# 4-POWER.net
KiCad netlist of a schematic drawn in Altium Designer
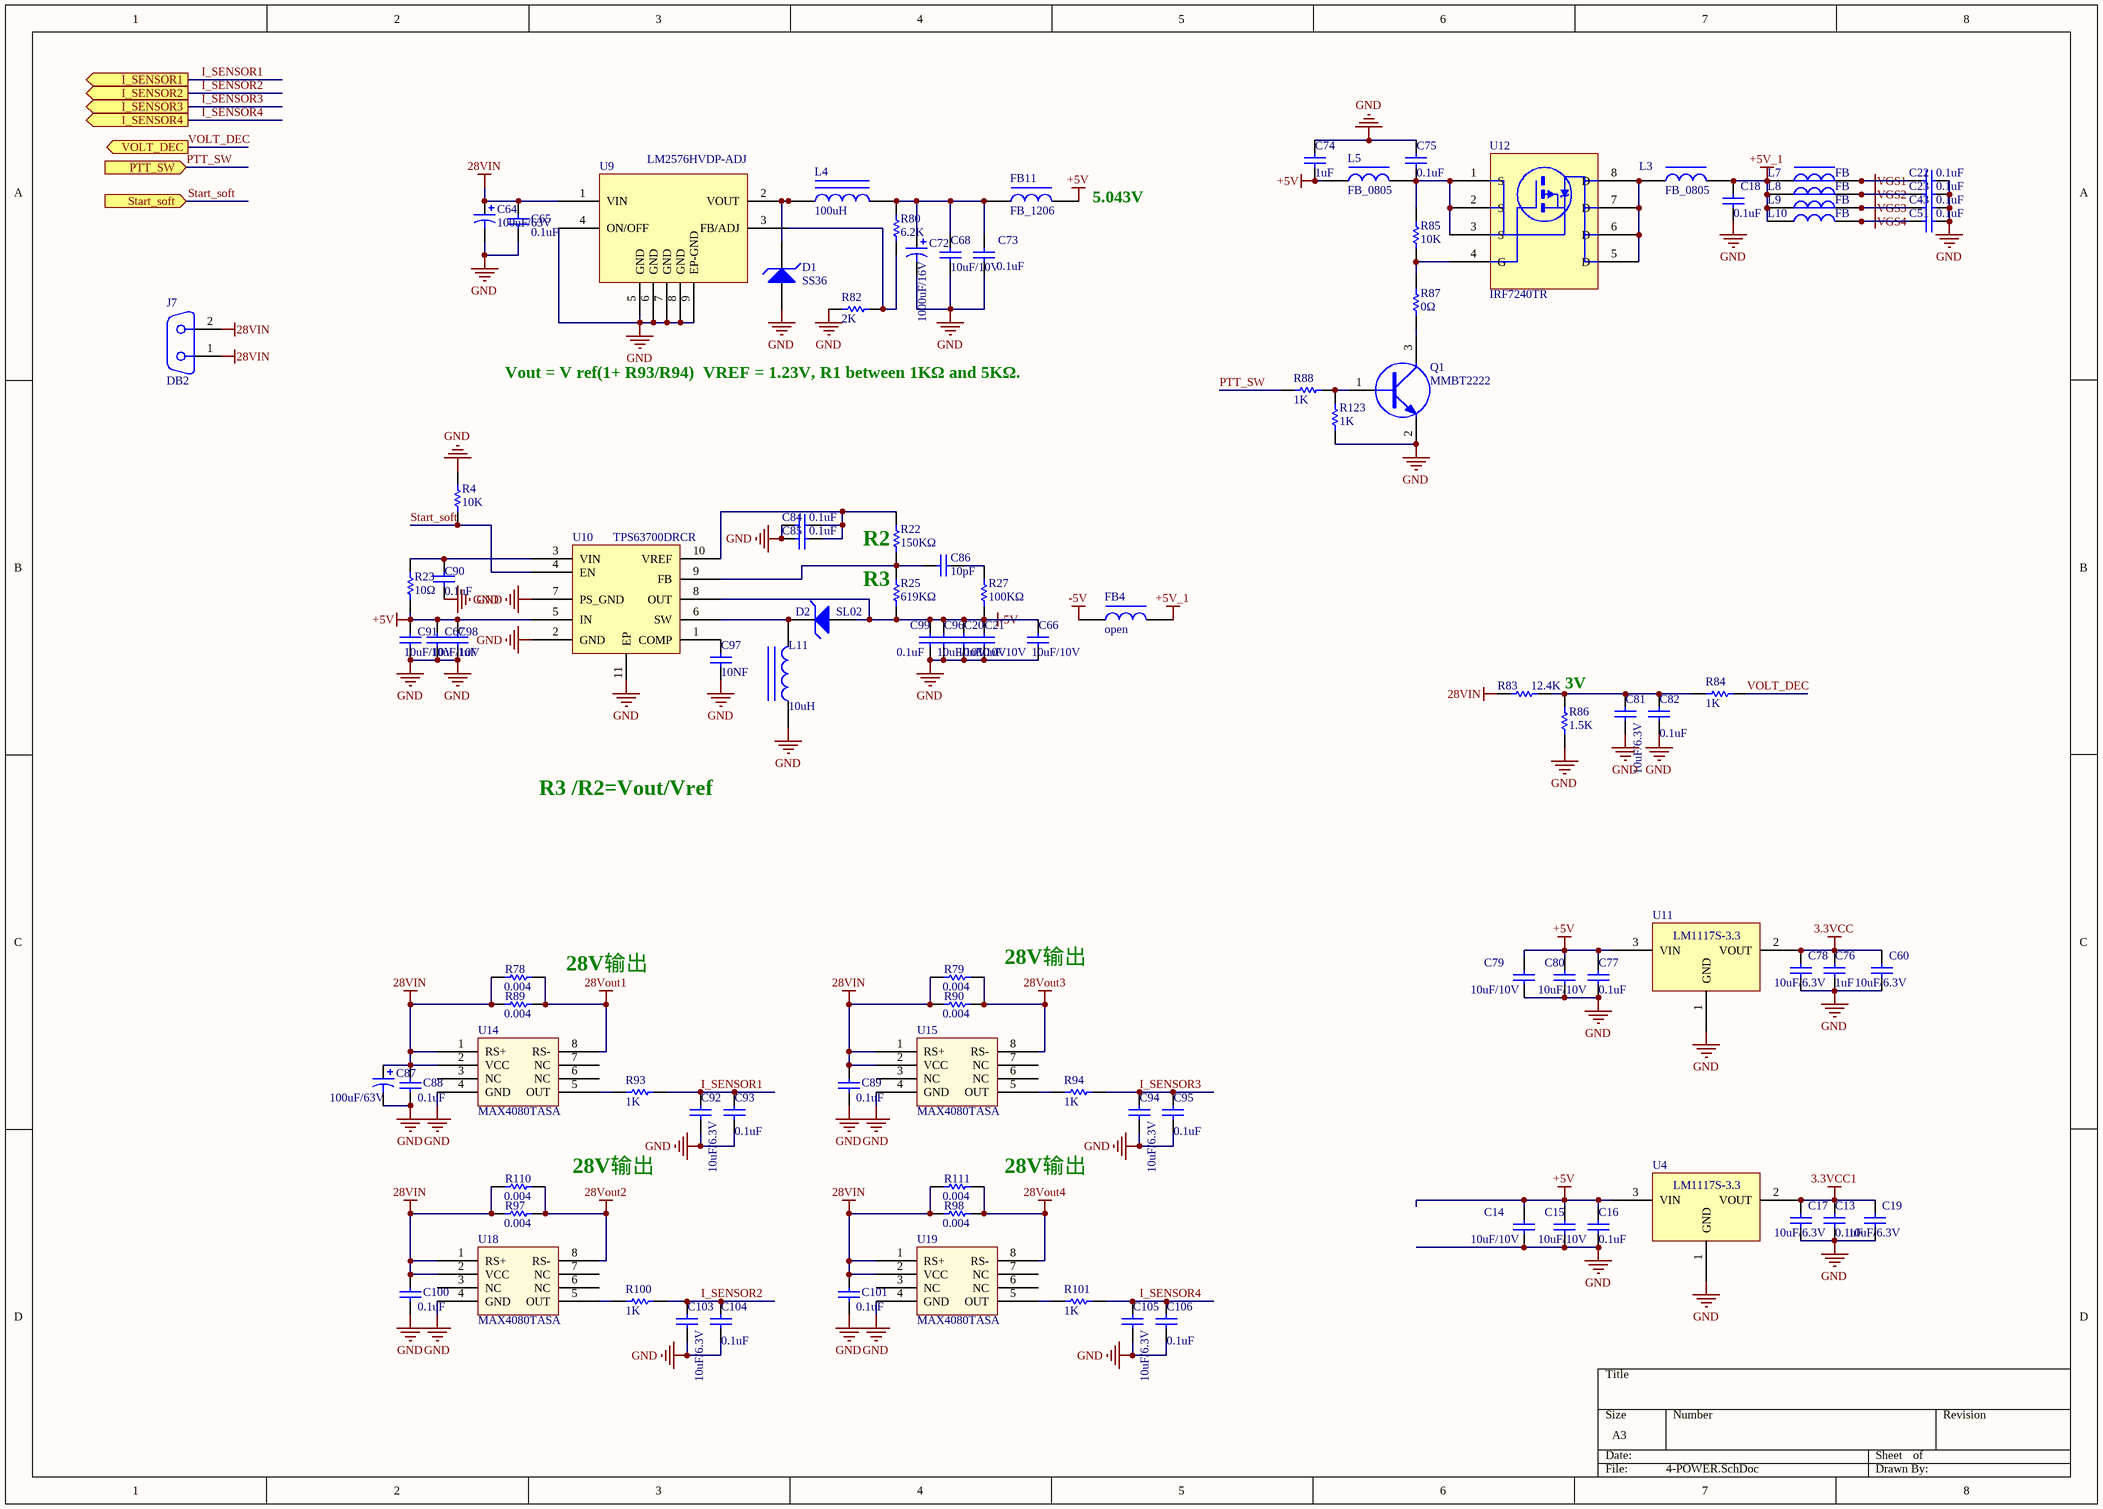
[diagram p0: 4-POWER.SchDoc]

(export (version "E")
  (design (tool "Eeschema 10.0.6"))
  (components
    (comp (ref "C13")
      (value "0.1uF")
      (footprint "C0603")
      (description "贴片电容_GRM188R61A105KA61D_1uF±10%,10V,0603")
      (libsource (lib "20贴片电容0603") (part "1uF贴片电容"))
    )
    (comp (ref "C14")
      (value "10uF/10V")
      (footprint "C0805")
      (description "贴片电容_GRM21BR61A106KE19L_10uF±10%,10V,0805")
      (libsource (lib "21贴片电容0805") (part "10uF贴片电容"))
    )
    (comp (ref "C15")
      (value "10uF/10V")
      (footprint "C0805")
      (description "贴片电容_GRM21BR61A106KE19L_10uF±10%,10V,0805")
      (libsource (lib "21贴片电容0805") (part "10uF贴片电容"))
    )
    (comp (ref "C16")
      (value "0.1uF")
      (footprint "C0603")
      (description "贴片电容_GRM188R71H104KA01D_0.1uF±10%,50V,0603")
      (libsource (lib "20贴片电容0603") (part "0.1uF贴片电容"))
    )
    (comp (ref "C17")
      (value "10uF/6.3V")
      (footprint "C0603")
      (description "贴片电容_GRM188R60J106ME47D_10uF±20%,6.3V,0603")
      (libsource (lib "20贴片电容0603") (part "10uF贴片电容"))
    )
    (comp (ref "C18")
      (value "0.1uF")
      (footprint "C0603")
      (description "GRM188R71H104KA01D")
      (fields (field (name "MPN") "MURATA"))
      (libsource (lib "20贴片电容0603") (part "0.1uF"))
    )
    (comp (ref "C19")
      (value "10uF/6.3V")
      (footprint "C0603")
      (description "贴片电容_GRM188R60J106ME47D_10uF±20%,6.3V,0603")
      (libsource (lib "20贴片电容0603") (part "10uF贴片电容"))
    )
    (comp (ref "C20")
      (value "10uF/10V")
      (footprint "C0805")
      (description "贴片电容_GRM21BR61A106KE19L_10uF±10%,10V,0805")
      (libsource (lib "21贴片电容0805") (part "10uF贴片电容"))
    )
    (comp (ref "C21")
      (value "10uF/10V")
      (footprint "C0805")
      (description "贴片电容_GRM21BR61A106KE19L_10uF±10%,10V,0805")
      (libsource (lib "21贴片电容0805") (part "10uF贴片电容"))
    )
    (comp (ref "C22")
      (value "0.1uF")
      (footprint "C0603")
      (description "GRM188R71H104KA01D")
      (fields (field (name "MPN") "MURATA"))
      (libsource (lib "20贴片电容0603") (part "0.1uF"))
    )
    (comp (ref "C23")
      (value "0.1uF")
      (footprint "C0603")
      (description "GRM188R71H104KA01D")
      (fields (field (name "MPN") "MURATA"))
      (libsource (lib "20贴片电容0603") (part "0.1uF"))
    )
    (comp (ref "C43")
      (value "0.1uF")
      (footprint "C0603")
      (description "GRM188R71H104KA01D")
      (fields (field (name "MPN") "MURATA"))
      (libsource (lib "20贴片电容0603") (part "0.1uF"))
    )
    (comp (ref "C51")
      (value "0.1uF")
      (footprint "C0603")
      (description "GRM188R71H104KA01D")
      (fields (field (name "MPN") "MURATA"))
      (libsource (lib "20贴片电容0603") (part "0.1uF"))
    )
    (comp (ref "C60")
      (value "10uF/6.3V")
      (footprint "C0603")
      (description "贴片电容_GRM188R60J106ME47D_10uF±20%,6.3V,0603")
      (libsource (lib "20贴片电容0603") (part "10uF贴片电容"))
    )
    (comp (ref "C64")
      (value "100uF/63V")
      (footprint "ECAP2SM_10R4x10R4")
      (description "贴片电解电容_VEJ101M1JTR-1010_100uF/63V,±20%,表贴D10*H10")
      (libsource (lib "24电解电容") (part "100uF/63V"))
    )
    (comp (ref "C65")
      (value "0.1uF")
      (footprint "C0603")
      (description "贴片电容_GRM188R71H104KA01D_0.1uF±10%,50V,0603")
      (libsource (lib "20贴片电容0603") (part "0.1uF贴片电容"))
    )
    (comp (ref "C66")
      (value "10uF/10V")
      (footprint "C0805")
      (description "贴片电容_GRM21BR61A106KE19L_10uF±10%,10V,0805")
      (libsource (lib "21贴片电容0805") (part "10uF贴片电容"))
    )
    (comp (ref "C67")
      (value "10uF/10V")
      (footprint "C0805")
      (description "贴片电容_GRM21BR61A106KE19L_10uF±10%,10V,0805")
      (libsource (lib "21贴片电容0805") (part "10uF贴片电容"))
    )
    (comp (ref "C68")
      (value "10uF/10V")
      (footprint "C0805")
      (description "贴片电容_GRM21BR61A106KE19L_10uF±10%,10V,0805")
      (libsource (lib "21贴片电容0805") (part "10uF贴片电容"))
    )
    (comp (ref "C72")
      (value "1000uF/16V")
      (footprint "ECAP2SM_10R4x10R4")
      (description "贴片电解电容_VE102M1CTR-1010_1000uF/16V,±20%,表贴10*10")
      (libsource (lib "24电解电容") (part "1000uF/16V"))
    )
    (comp (ref "C73")
      (value "0.1uF")
      (footprint "C0603")
      (description "贴片电容_GRM188R71H104KA01D_0.1uF±10%,50V,0603")
      (libsource (lib "20贴片电容0603") (part "0.1uF贴片电容"))
    )
    (comp (ref "C74")
      (value "1uF")
      (footprint "C0603")
      (description "贴片电容_GRM188R61A105KA61D_1uF±10%,10V,0603")
      (libsource (lib "20贴片电容0603") (part "1uF贴片电容"))
    )
    (comp (ref "C75")
      (value "0.1uF")
      (footprint "C0603")
      (description "贴片电容_GRM188R71H104KA01D_0.1uF±10%,50V,0603")
      (libsource (lib "20贴片电容0603") (part "0.1uF贴片电容"))
    )
    (comp (ref "C76")
      (value "1uF")
      (footprint "C0603")
      (description "贴片电容_GRM188R61A105KA61D_1uF±10%,10V,0603")
      (libsource (lib "20贴片电容0603") (part "1uF贴片电容"))
    )
    (comp (ref "C77")
      (value "0.1uF")
      (footprint "C0603")
      (description "贴片电容_GRM188R71H104KA01D_0.1uF±10%,50V,0603")
      (libsource (lib "20贴片电容0603") (part "0.1uF贴片电容"))
    )
    (comp (ref "C78")
      (value "10uF/6.3V")
      (footprint "C0603")
      (description "贴片电容_GRM188R60J106ME47D_10uF±20%,6.3V,0603")
      (libsource (lib "20贴片电容0603") (part "10uF贴片电容"))
    )
    (comp (ref "C79")
      (value "10uF/10V")
      (footprint "C0805")
      (description "贴片电容_GRM21BR61A106KE19L_10uF±10%,10V,0805")
      (libsource (lib "21贴片电容0805") (part "10uF贴片电容"))
    )
    (comp (ref "C80")
      (value "10uF/10V")
      (footprint "C0805")
      (description "贴片电容_GRM21BR61A106KE19L_10uF±10%,10V,0805")
      (libsource (lib "21贴片电容0805") (part "10uF贴片电容"))
    )
    (comp (ref "C81")
      (value "10uF/6.3V")
      (footprint "C0603")
      (description "贴片电容_GRM188R60J106ME47D_10uF±20%,6.3V,0603")
      (libsource (lib "20贴片电容0603") (part "10uF贴片电容"))
    )
    (comp (ref "C82")
      (value "0.1uF")
      (footprint "C0603")
      (description "贴片电容_GRM188R71H104KA01D_0.1uF±10%,50V,0603")
      (libsource (lib "20贴片电容0603") (part "0.1uF贴片电容"))
    )
    (comp (ref "C84")
      (value "0.1uF")
      (footprint "C0603")
      (description "GRM188R71H104KA01D")
      (fields (field (name "MPN") "MURATA"))
      (libsource (lib "20贴片电容0603") (part "0.1uF"))
    )
    (comp (ref "C85")
      (value "0.1uF")
      (footprint "C0603")
      (description "GRM188R71H104KA01D")
      (fields (field (name "MPN") "MURATA"))
      (libsource (lib "20贴片电容0603") (part "0.1uF"))
    )
    (comp (ref "C86")
      (value "10pF")
      (footprint "C0603")
      (description "贴片电容_0603CG100J500NT_10pF±5%,50V,0603")
      (libsource (lib "20贴片电容0603") (part "10pF贴片电容"))
    )
    (comp (ref "C87")
      (value "100uF/63V")
      (footprint "ECAP2SM_10R4x10R4")
      (description "贴片电解电容_VEJ101M1JTR-1010_100uF/63V,±20%,表贴D10*H10")
      (libsource (lib "24电解电容") (part "100uF/63V"))
    )
    (comp (ref "C88")
      (value "0.1uF")
      (footprint "C0603")
      (description "贴片电容_GRM188R71H104KA01D_0.1uF±10%,50V,0603")
      (libsource (lib "20贴片电容0603") (part "0.1uF贴片电容"))
    )
    (comp (ref "C89")
      (value "0.1uF")
      (footprint "C0603")
      (description "贴片电容_GRM188R71H104KA01D_0.1uF±10%,50V,0603")
      (libsource (lib "20贴片电容0603") (part "0.1uF贴片电容"))
    )
    (comp (ref "C90")
      (value "0.1uF")
      (footprint "C0603")
      (description "GRM188R71H104KA01D")
      (fields (field (name "MPN") "MURATA"))
      (libsource (lib "20贴片电容0603") (part "0.1uF"))
    )
    (comp (ref "C91")
      (value "10uF/10V")
      (footprint "C0805")
      (description "贴片电容_GRM21BR61A106KE19L_10uF±10%,10V,0805")
      (libsource (lib "21贴片电容0805") (part "10uF贴片电容"))
    )
    (comp (ref "C92")
      (value "10uF/6.3V")
      (footprint "C0603")
      (description "贴片电容_GRM188R60J106ME47D_10uF±20%,6.3V,0603")
      (libsource (lib "20贴片电容0603") (part "10uF贴片电容"))
    )
    (comp (ref "C93")
      (value "0.1uF")
      (footprint "C0603")
      (description "贴片电容_GRM188R71H104KA01D_0.1uF±10%,50V,0603")
      (libsource (lib "20贴片电容0603") (part "0.1uF贴片电容"))
    )
    (comp (ref "C94")
      (value "10uF/6.3V")
      (footprint "C0603")
      (description "贴片电容_GRM188R60J106ME47D_10uF±20%,6.3V,0603")
      (libsource (lib "20贴片电容0603") (part "10uF贴片电容"))
    )
    (comp (ref "C95")
      (value "0.1uF")
      (footprint "C0603")
      (description "贴片电容_GRM188R71H104KA01D_0.1uF±10%,50V,0603")
      (libsource (lib "20贴片电容0603") (part "0.1uF贴片电容"))
    )
    (comp (ref "C96")
      (value "10uF/10V")
      (footprint "C0805")
      (description "贴片电容_GRM21BR61A106KE19L_10uF±10%,10V,0805")
      (libsource (lib "21贴片电容0805") (part "10uF贴片电容"))
    )
    (comp (ref "C97")
      (value "10NF")
      (footprint "C0603")
      (description "0603,10NF,50V,±10％,X7R")
      (libsource (lib "20贴片电容0603") (part "0.1uF"))
    )
    (comp (ref "C98") (value "1uF") (footprint "C0603") (libsource (lib "20贴片电容0603") (part "0.1uF")))
    (comp (ref "C99")
      (value "0.1uF")
      (footprint "C0603")
      (description "GRM188R71H104KA01D")
      (fields (field (name "MPN") "MURATA"))
      (libsource (lib "20贴片电容0603") (part "0.1uF"))
    )
    (comp (ref "C100")
      (value "0.1uF")
      (footprint "C0603")
      (description "贴片电容_GRM188R71H104KA01D_0.1uF±10%,50V,0603")
      (libsource (lib "20贴片电容0603") (part "0.1uF贴片电容"))
    )
    (comp (ref "C101")
      (value "0.1uF")
      (footprint "C0603")
      (description "贴片电容_GRM188R71H104KA01D_0.1uF±10%,50V,0603")
      (libsource (lib "20贴片电容0603") (part "0.1uF贴片电容"))
    )
    (comp (ref "C103")
      (value "10uF/6.3V")
      (footprint "C0603")
      (description "贴片电容_GRM188R60J106ME47D_10uF±20%,6.3V,0603")
      (libsource (lib "20贴片电容0603") (part "10uF贴片电容"))
    )
    (comp (ref "C104")
      (value "0.1uF")
      (footprint "C0603")
      (description "贴片电容_GRM188R71H104KA01D_0.1uF±10%,50V,0603")
      (libsource (lib "20贴片电容0603") (part "0.1uF贴片电容"))
    )
    (comp (ref "C105")
      (value "10uF/6.3V")
      (footprint "C0603")
      (description "贴片电容_GRM188R60J106ME47D_10uF±20%,6.3V,0603")
      (libsource (lib "20贴片电容0603") (part "10uF贴片电容"))
    )
    (comp (ref "C106")
      (value "0.1uF")
      (footprint "C0603")
      (description "贴片电容_GRM188R71H104KA01D_0.1uF±10%,50V,0603")
      (libsource (lib "20贴片电容0603") (part "0.1uF贴片电容"))
    )
    (comp (ref "D1")
      (value "SS36")
      (footprint "DO-214AC")
      (description "肖特基整流二极管_SS36_封装SMA,3A/60V")
      (libsource (lib "40二极管") (part "肖特基整流二极管_SS36"))
    )
    (comp (ref "D2")
      (value "SL02")
      (footprint "SL02")
      (description "肖特基整流二极管_SL02_1.1A/20V")
      (libsource (lib "40二极管") (part "肖特基整流二极管_SS36"))
    )
    (comp (ref "FB4")
      (value "open")
      (footprint "L0805")
      (description "贴片磁珠_600R,0805")
      (libsource (lib "33贴片磁珠0805") (part "0805贴片磁珠"))
    )
    (comp (ref "FB11")
      (value "FB_1206")
      (footprint "L1206")
      (description "贴片磁珠_30R,6A,1206")
      (libsource (lib "34贴片磁珠1206") (part "1206贴片磁珠"))
    )
    (comp (ref "J7")
      (value "DB2")
      (footprint "DB2TM-VM")
      (description "连接器_DB2公头,电源接头")
      (libsource (lib "91连接器") (part "DB2公头座子"))
    )
    (comp (ref "L3")
      (value "FB_0805")
      (footprint "L0805")
      (description "贴片磁珠_600R,0805")
      (libsource (lib "33贴片磁珠0805") (part "0805贴片磁珠"))
    )
    (comp (ref "L4")
      (value "100uH")
      (footprint "PL2SM-12R5x12R5")
      (description "贴片功率电感_SLF12575T-101M1R9-PF_100uH±20%,额定电流1.9A,12.5x12.5")
      (libsource (lib "32贴片功率电感") (part "100uH贴片功率电感"))
    )
    (comp (ref "L5")
      (value "FB_0805")
      (footprint "L0805")
      (description "贴片磁珠_600R,0805")
      (libsource (lib "33贴片磁珠0805") (part "0805贴片磁珠"))
    )
    (comp (ref "L7")
      (value "FB")
      (footprint "L0805")
      (description "贴片磁珠_600R,0805")
      (libsource (lib "33贴片磁珠0805") (part "0805贴片磁珠"))
    )
    (comp (ref "L8")
      (value "FB")
      (footprint "L0805")
      (description "贴片磁珠_600R,0805")
      (libsource (lib "33贴片磁珠0805") (part "0805贴片磁珠"))
    )
    (comp (ref "L9")
      (value "FB")
      (footprint "L0805")
      (description "贴片磁珠_600R,0805")
      (libsource (lib "33贴片磁珠0805") (part "0805贴片磁珠"))
    )
    (comp (ref "L10")
      (value "FB")
      (footprint "L0805")
      (description "贴片磁珠_600R,0805")
      (libsource (lib "33贴片磁珠0805") (part "0805贴片磁珠"))
    )
    (comp (ref "L11")
      (value "10uH")
      (footprint "PL2SM-3R0x3R0")
      (description "SLF6025-10uH")
      (libsource (lib "35贴片功率电感") (part "SLF6025T-100M1R0-PF"))
    )
    (comp (ref "Q1")
      (value "MMBT2222")
      (footprint "SOT23-3")
      (description "NPN三极管_MMBT2222_表贴SOT23")
      (libsource (lib "50三极管") (part "MMBT2222"))
    )
    (comp (ref "R4")
      (value "10K")
      (footprint "R0603")
      (description "贴片电阻_10K±5%,0603")
      (libsource (lib "10贴片电阻0603") (part "10K贴片电阻"))
    )
    (comp (ref "R22") (value "150KΩ") (footprint "R0603") (libsource (lib "10贴片电阻0603") (part "10Ω贴片电阻")))
    (comp (ref "R23")
      (value "10Ω")
      (footprint "R0603")
      (description "贴片电阻_10Ω±5%,0603")
      (libsource (lib "10贴片电阻0603") (part "10Ω贴片电阻"))
    )
    (comp (ref "R25") (value "619KΩ") (footprint "R0603") (libsource (lib "10贴片电阻0603") (part "10Ω贴片电阻")))
    (comp (ref "R27") (value "100KΩ") (footprint "R0603") (libsource (lib "10贴片电阻0603") (part "10Ω贴片电阻")))
    (comp (ref "R78")
      (value "0.004")
      (footprint "R2512")
      (description "贴片电阻_LR12DTDSR004_0.004±5%,2W,2512")
      (libsource (lib "15贴片检流电阻") (part "0.004Ω检流电阻-大封装"))
    )
    (comp (ref "R79")
      (value "0.004")
      (footprint "R2512")
      (description "贴片电阻_LR12DTDSR004_0.004±5%,2W,2512")
      (libsource (lib "15贴片检流电阻") (part "0.004Ω检流电阻-大封装"))
    )
    (comp (ref "R80")
      (value "6.2K")
      (footprint "R0603")
      (description "贴片电阻_6.2K±5%,0603")
      (libsource (lib "10贴片电阻0603") (part "6.2K贴片电阻"))
    )
    (comp (ref "R82")
      (value "2K")
      (footprint "R0603")
      (description "贴片电阻_2K±5%,0603")
      (libsource (lib "10贴片电阻0603") (part "2K贴片电阻"))
    )
    (comp (ref "R83")
      (value "12.4K")
      (footprint "R0603")
      (description "贴片电阻_12.4K±1%,0603")
      (libsource (lib "10贴片电阻0603") (part "12.4K贴片电阻"))
    )
    (comp (ref "R84")
      (value "1K")
      (footprint "C0603")
      (description "贴片电阻_1K±5%,0603")
      (libsource (lib "10贴片电阻0603") (part "1K贴片电阻"))
    )
    (comp (ref "R85")
      (value "10K")
      (footprint "R0603")
      (description "贴片电阻_10K±5%,0603")
      (libsource (lib "10贴片电阻0603") (part "10K贴片电阻"))
    )
    (comp (ref "R86")
      (value "1.5K")
      (footprint "R0603")
      (description "贴片电阻_1.5K±5%,0603")
      (libsource (lib "10贴片电阻0603") (part "1.5K贴片电阻"))
    )
    (comp (ref "R87")
      (value "0Ω")
      (footprint "R0603")
      (description "贴片电阻_0Ω±5%,0603")
      (libsource (lib "10贴片电阻0603") (part "0Ω贴片电阻"))
    )
    (comp (ref "R88")
      (value "1K")
      (footprint "R0603")
      (description "贴片电阻_1K±5%,0603")
      (libsource (lib "10贴片电阻0603") (part "1K贴片电阻"))
    )
    (comp (ref "R89")
      (value "0.004")
      (footprint "R2512")
      (description "贴片电阻_LR12DTDSR004_0.004±5%,2W,2512")
      (libsource (lib "15贴片检流电阻") (part "0.004Ω检流电阻-大封装"))
    )
    (comp (ref "R90")
      (value "0.004")
      (footprint "R2512")
      (description "贴片电阻_LR12DTDSR004_0.004±5%,2W,2512")
      (libsource (lib "15贴片检流电阻") (part "0.004Ω检流电阻-大封装"))
    )
    (comp (ref "R93")
      (value "1K")
      (footprint "R0603")
      (description "贴片电阻_1K±5%,0603")
      (libsource (lib "10贴片电阻0603") (part "1K贴片电阻"))
    )
    (comp (ref "R94")
      (value "1K")
      (footprint "R0603")
      (description "贴片电阻_1K±5%,0603")
      (libsource (lib "10贴片电阻0603") (part "1K贴片电阻"))
    )
    (comp (ref "R97")
      (value "0.004")
      (footprint "R2512")
      (description "贴片电阻_LR12DTDSR004_0.004±5%,2W,2512")
      (libsource (lib "15贴片检流电阻") (part "0.004Ω检流电阻-大封装"))
    )
    (comp (ref "R98")
      (value "0.004")
      (footprint "R2512")
      (description "贴片电阻_LR12DTDSR004_0.004±5%,2W,2512")
      (libsource (lib "15贴片检流电阻") (part "0.004Ω检流电阻-大封装"))
    )
    (comp (ref "R100")
      (value "1K")
      (footprint "R0603")
      (description "贴片电阻_1K±5%,0603")
      (libsource (lib "10贴片电阻0603") (part "1K贴片电阻"))
    )
    (comp (ref "R101")
      (value "1K")
      (footprint "R0603")
      (description "贴片电阻_1K±5%,0603")
      (libsource (lib "10贴片电阻0603") (part "1K贴片电阻"))
    )
    (comp (ref "R110")
      (value "0.004")
      (footprint "R2512")
      (description "贴片电阻_LR12DTDSR004_0.004±5%,2W,2512")
      (libsource (lib "15贴片检流电阻") (part "0.004Ω检流电阻-大封装"))
    )
    (comp (ref "R111")
      (value "0.004")
      (footprint "R2512")
      (description "贴片电阻_LR12DTDSR004_0.004±5%,2W,2512")
      (libsource (lib "15贴片检流电阻") (part "0.004Ω检流电阻-大封装"))
    )
    (comp (ref "R123")
      (value "1K")
      (footprint "R0603")
      (description "贴片电阻_1K±5%,0603")
      (libsource (lib "10贴片电阻0603") (part "1K贴片电阻"))
    )
    (comp (ref "U4")
      (value "LM1117S-3.3")
      (footprint "SOT-223")
      (description "LDO_LM1117S-3.3_1A输出,SOT223")
      (libsource (lib "78电源芯片") (part "LM1117S-3.3"))
    )
    (comp (ref "U9")
      (value "LM2576HVDP-ADJ")
      (footprint "SOIC8_1R27_3R9x4R9-1")
      (description "稳压集成电路_LM2576HVDP-ADJ_3A输出,SOIC8")
      (libsource (lib "78电源芯片") (part "LM2576HVDP-ADJ"))
    )
    (comp (ref "U10")
      (value "TPS63700DRCR")
      (footprint "VSON10-0R5-3x3")
      (description "负压转换器_TPS63700DRCR_360mA输出,VSON-10")
      (libsource (lib "78电源芯片") (part "TPS63700DRCR"))
    )
    (comp (ref "U11")
      (value "LM1117S-3.3")
      (footprint "SOT-223")
      (description "LDO_LM1117S-3.3_1A输出,SOT223")
      (libsource (lib "78电源芯片") (part "LM1117S-3.3"))
    )
    (comp (ref "U12")
      (value "IRF7240TR")
      (footprint "SOIC8_1R27_3R9x4R9")
      (description "P-MOSFET_IRF7240TR_SOIC8")
      (libsource (lib "51场效应管") (part "IRF7240TR"))
    )
    (comp (ref "U14")
      (value "MAX4080TASA")
      (footprint "SOIC8_1R27_3R9x4R9")
      (description "电流检测放大器_MAX4080TASA_SOIC8")
      (libsource (lib "79电流检测芯片") (part "MAX4080TASA"))
    )
    (comp (ref "U15")
      (value "MAX4080TASA")
      (footprint "SOIC8_1R27_3R9x4R9")
      (description "电流检测放大器_MAX4080TASA_SOIC8")
      (libsource (lib "79电流检测芯片") (part "MAX4080TASA"))
    )
    (comp (ref "U18")
      (value "MAX4080TASA")
      (footprint "SOIC8_1R27_3R9x4R9")
      (description "电流检测放大器_MAX4080TASA_SOIC8")
      (libsource (lib "79电流检测芯片") (part "MAX4080TASA"))
    )
    (comp (ref "U19")
      (value "MAX4080TASA")
      (footprint "SOIC8_1R27_3R9x4R9")
      (description "电流检测放大器_MAX4080TASA_SOIC8")
      (libsource (lib "79电流检测芯片") (part "MAX4080TASA"))
    )
  )
  (nets
    (net (code "1") (name "+5V") (class "Default")
      (node (ref "C14") (pin "2") (pinfunction "2_2") (pintype "passive"))
      (node (ref "C15") (pin "2") (pinfunction "2_2") (pintype "passive"))
      (node (ref "C16") (pin "2") (pinfunction "2_2") (pintype "passive"))
      (node (ref "C67") (pin "2") (pinfunction "2_2") (pintype "passive"))
      (node (ref "C74") (pin "1") (pinfunction "1_1") (pintype "passive"))
      (node (ref "C77") (pin "2") (pinfunction "2_2") (pintype "passive"))
      (node (ref "C79") (pin "2") (pinfunction "2_2") (pintype "passive"))
      (node (ref "C80") (pin "2") (pinfunction "2_2") (pintype "passive"))
      (node (ref "C91") (pin "2") (pinfunction "2_2") (pintype "passive"))
      (node (ref "C98") (pin "2") (pinfunction "2_2") (pintype "passive"))
      (node (ref "FB11") (pin "2") (pinfunction "2_2") (pintype "passive"))
      (node (ref "L5") (pin "1") (pinfunction "1_1") (pintype "passive"))
      (node (ref "R23") (pin "1") (pinfunction "1_1") (pintype "passive"))
      (node (ref "U10") (pin "5") (pinfunction "IN_5") (pintype "passive"))
      (node (ref "U11") (pin "3") (pinfunction "VIN_3") (pintype "passive"))
      (node (ref "U4") (pin "3") (pinfunction "VIN_3") (pintype "passive"))
    )
    (net (code "2") (name "+5V_1") (class "Default")
      (node (ref "C18") (pin "2") (pinfunction "2_2") (pintype "passive"))
      (node (ref "FB4") (pin "2") (pinfunction "2_2") (pintype "passive"))
      (node (ref "L10") (pin "1") (pinfunction "1_1") (pintype "passive"))
      (node (ref "L3") (pin "2") (pinfunction "2_2") (pintype "passive"))
      (node (ref "L7") (pin "1") (pinfunction "1_1") (pintype "passive"))
      (node (ref "L8") (pin "1") (pinfunction "1_1") (pintype "passive"))
      (node (ref "L9") (pin "1") (pinfunction "1_1") (pintype "passive"))
    )
    (net (code "3") (name "-5V") (class "Default")
      (node (ref "C20") (pin "2") (pinfunction "2_2") (pintype "passive"))
      (node (ref "C21") (pin "2") (pinfunction "2_2") (pintype "passive"))
      (node (ref "C66") (pin "2") (pinfunction "2_2") (pintype "passive"))
      (node (ref "C96") (pin "2") (pinfunction "2_2") (pintype "passive"))
      (node (ref "C99") (pin "2") (pinfunction "2_2") (pintype "passive"))
      (node (ref "D2") (pin "1") (pinfunction "A_1") (pintype "passive"))
      (node (ref "FB4") (pin "1") (pinfunction "1_1") (pintype "passive"))
      (node (ref "R25") (pin "1") (pinfunction "1_1") (pintype "passive"))
      (node (ref "R27") (pin "1") (pinfunction "1_1") (pintype "passive"))
      (node (ref "U10") (pin "8") (pinfunction "OUT_8") (pintype "passive"))
    )
    (net (code "4") (name "/I_SENSOR1") (class "Default")
      (node (ref "C92") (pin "2") (pinfunction "2_2") (pintype "passive"))
      (node (ref "C93") (pin "2") (pinfunction "2_2") (pintype "passive"))
      (node (ref "R93") (pin "2") (pinfunction "2_2") (pintype "passive"))
    )
    (net (code "5") (name "/I_SENSOR2") (class "Default")
      (node (ref "C103") (pin "2") (pinfunction "2_2") (pintype "passive"))
      (node (ref "C104") (pin "2") (pinfunction "2_2") (pintype "passive"))
      (node (ref "R100") (pin "2") (pinfunction "2_2") (pintype "passive"))
    )
    (net (code "6") (name "/I_SENSOR3") (class "Default")
      (node (ref "C94") (pin "2") (pinfunction "2_2") (pintype "passive"))
      (node (ref "C95") (pin "2") (pinfunction "2_2") (pintype "passive"))
      (node (ref "R94") (pin "2") (pinfunction "2_2") (pintype "passive"))
    )
    (net (code "7") (name "/I_SENSOR4") (class "Default")
      (node (ref "C105") (pin "2") (pinfunction "2_2") (pintype "passive"))
      (node (ref "C106") (pin "2") (pinfunction "2_2") (pintype "passive"))
      (node (ref "R101") (pin "2") (pinfunction "2_2") (pintype "passive"))
    )
    (net (code "8") (name "/PTT_SW") (class "Default")
      (node (ref "R88") (pin "1") (pinfunction "1_1") (pintype "passive"))
    )
    (net (code "9") (name "/Start_soft") (class "Default")
      (node (ref "R4") (pin "1") (pinfunction "1_1") (pintype "passive"))
      (node (ref "U10") (pin "4") (pinfunction "EN_4") (pintype "passive"))
    )
    (net (code "10") (name "/VOLT_DEC") (class "Default")
      (node (ref "R84") (pin "1") (pinfunction "1_1") (pintype "passive"))
    )
    (net (code "11") (name "3.3VCC") (class "Default")
      (node (ref "C60") (pin "2") (pinfunction "2_2") (pintype "passive"))
      (node (ref "C76") (pin "2") (pinfunction "2_2") (pintype "passive"))
      (node (ref "C78") (pin "2") (pinfunction "2_2") (pintype "passive"))
      (node (ref "U11") (pin "2") (pinfunction "VOUT_2") (pintype "passive"))
    )
    (net (code "12") (name "3.3VCC1") (class "Default")
      (node (ref "C13") (pin "2") (pinfunction "2_2") (pintype "passive"))
      (node (ref "C17") (pin "2") (pinfunction "2_2") (pintype "passive"))
      (node (ref "C19") (pin "2") (pinfunction "2_2") (pintype "passive"))
      (node (ref "U4") (pin "2") (pinfunction "VOUT_2") (pintype "passive"))
    )
    (net (code "13") (name "28VIN") (class "Default")
      (node (ref "C100") (pin "2") (pinfunction "2_2") (pintype "passive"))
      (node (ref "C101") (pin "2") (pinfunction "2_2") (pintype "passive"))
      (node (ref "C64") (pin "1") (pinfunction "1_1") (pintype "passive"))
      (node (ref "C65") (pin "2") (pinfunction "2_2") (pintype "passive"))
      (node (ref "C87") (pin "1") (pinfunction "1_1") (pintype "passive"))
      (node (ref "C88") (pin "2") (pinfunction "2_2") (pintype "passive"))
      (node (ref "C89") (pin "2") (pinfunction "2_2") (pintype "passive"))
      (node (ref "J7") (pin "1") (pinfunction "1_1") (pintype "passive"))
      (node (ref "J7") (pin "2") (pinfunction "2_2") (pintype "passive"))
      (node (ref "R110") (pin "1") (pinfunction "1_1") (pintype "passive"))
      (node (ref "R111") (pin "1") (pinfunction "1_1") (pintype "passive"))
      (node (ref "R78") (pin "1") (pinfunction "1_1") (pintype "passive"))
      (node (ref "R79") (pin "1") (pinfunction "1_1") (pintype "passive"))
      (node (ref "R83") (pin "1") (pinfunction "1_1") (pintype "passive"))
      (node (ref "R89") (pin "1") (pinfunction "1_1") (pintype "passive"))
      (node (ref "R90") (pin "1") (pinfunction "1_1") (pintype "passive"))
      (node (ref "R97") (pin "1") (pinfunction "1_1") (pintype "passive"))
      (node (ref "R98") (pin "1") (pinfunction "1_1") (pintype "passive"))
      (node (ref "U14") (pin "1") (pinfunction "RS+_1") (pintype "passive"))
      (node (ref "U14") (pin "2") (pinfunction "VCC_2") (pintype "passive"))
      (node (ref "U15") (pin "1") (pinfunction "RS+_1") (pintype "passive"))
      (node (ref "U15") (pin "2") (pinfunction "VCC_2") (pintype "passive"))
      (node (ref "U18") (pin "1") (pinfunction "RS+_1") (pintype "passive"))
      (node (ref "U18") (pin "2") (pinfunction "VCC_2") (pintype "passive"))
      (node (ref "U19") (pin "1") (pinfunction "RS+_1") (pintype "passive"))
      (node (ref "U19") (pin "2") (pinfunction "VCC_2") (pintype "passive"))
      (node (ref "U9") (pin "1") (pinfunction "VIN_1") (pintype "passive"))
    )
    (net (code "14") (name "28Vout1") (class "Default")
      (node (ref "R78") (pin "2") (pinfunction "2_2") (pintype "passive"))
      (node (ref "R89") (pin "2") (pinfunction "2_2") (pintype "passive"))
      (node (ref "U14") (pin "8") (pinfunction "RS-_8") (pintype "passive"))
    )
    (net (code "15") (name "28Vout2") (class "Default")
      (node (ref "R110") (pin "2") (pinfunction "2_2") (pintype "passive"))
      (node (ref "R97") (pin "2") (pinfunction "2_2") (pintype "passive"))
      (node (ref "U18") (pin "8") (pinfunction "RS-_8") (pintype "passive"))
    )
    (net (code "16") (name "28Vout3") (class "Default")
      (node (ref "R79") (pin "2") (pinfunction "2_2") (pintype "passive"))
      (node (ref "R90") (pin "2") (pinfunction "2_2") (pintype "passive"))
      (node (ref "U15") (pin "8") (pinfunction "RS-_8") (pintype "passive"))
    )
    (net (code "17") (name "28Vout4") (class "Default")
      (node (ref "R111") (pin "2") (pinfunction "2_2") (pintype "passive"))
      (node (ref "R98") (pin "2") (pinfunction "2_2") (pintype "passive"))
      (node (ref "U19") (pin "8") (pinfunction "RS-_8") (pintype "passive"))
    )
    (net (code "18") (name "GND") (class "Default")
      (node (ref "C100") (pin "1") (pinfunction "1_1") (pintype "passive"))
      (node (ref "C101") (pin "1") (pinfunction "1_1") (pintype "passive"))
      (node (ref "C103") (pin "1") (pinfunction "1_1") (pintype "passive"))
      (node (ref "C104") (pin "1") (pinfunction "1_1") (pintype "passive"))
      (node (ref "C105") (pin "1") (pinfunction "1_1") (pintype "passive"))
      (node (ref "C106") (pin "1") (pinfunction "1_1") (pintype "passive"))
      (node (ref "C13") (pin "1") (pinfunction "1_1") (pintype "passive"))
      (node (ref "C14") (pin "1") (pinfunction "1_1") (pintype "passive"))
      (node (ref "C15") (pin "1") (pinfunction "1_1") (pintype "passive"))
      (node (ref "C16") (pin "1") (pinfunction "1_1") (pintype "passive"))
      (node (ref "C17") (pin "1") (pinfunction "1_1") (pintype "passive"))
      (node (ref "C18") (pin "1") (pinfunction "1_1") (pintype "passive"))
      (node (ref "C19") (pin "1") (pinfunction "1_1") (pintype "passive"))
      (node (ref "C20") (pin "1") (pinfunction "1_1") (pintype "passive"))
      (node (ref "C21") (pin "1") (pinfunction "1_1") (pintype "passive"))
      (node (ref "C22") (pin "2") (pinfunction "2_2") (pintype "passive"))
      (node (ref "C23") (pin "2") (pinfunction "2_2") (pintype "passive"))
      (node (ref "C43") (pin "2") (pinfunction "2_2") (pintype "passive"))
      (node (ref "C51") (pin "2") (pinfunction "2_2") (pintype "passive"))
      (node (ref "C60") (pin "1") (pinfunction "1_1") (pintype "passive"))
      (node (ref "C64") (pin "2") (pinfunction "2_2") (pintype "passive"))
      (node (ref "C65") (pin "1") (pinfunction "1_1") (pintype "passive"))
      (node (ref "C66") (pin "1") (pinfunction "1_1") (pintype "passive"))
      (node (ref "C67") (pin "1") (pinfunction "1_1") (pintype "passive"))
      (node (ref "C68") (pin "1") (pinfunction "1_1") (pintype "passive"))
      (node (ref "C72") (pin "2") (pinfunction "2_2") (pintype "passive"))
      (node (ref "C73") (pin "1") (pinfunction "1_1") (pintype "passive"))
      (node (ref "C74") (pin "2") (pinfunction "2_2") (pintype "passive"))
      (node (ref "C75") (pin "2") (pinfunction "2_2") (pintype "passive"))
      (node (ref "C76") (pin "1") (pinfunction "1_1") (pintype "passive"))
      (node (ref "C77") (pin "1") (pinfunction "1_1") (pintype "passive"))
      (node (ref "C78") (pin "1") (pinfunction "1_1") (pintype "passive"))
      (node (ref "C79") (pin "1") (pinfunction "1_1") (pintype "passive"))
      (node (ref "C80") (pin "1") (pinfunction "1_1") (pintype "passive"))
      (node (ref "C81") (pin "1") (pinfunction "1_1") (pintype "passive"))
      (node (ref "C82") (pin "1") (pinfunction "1_1") (pintype "passive"))
      (node (ref "C84") (pin "2") (pinfunction "2_2") (pintype "passive"))
      (node (ref "C85") (pin "2") (pinfunction "2_2") (pintype "passive"))
      (node (ref "C87") (pin "2") (pinfunction "2_2") (pintype "passive"))
      (node (ref "C88") (pin "1") (pinfunction "1_1") (pintype "passive"))
      (node (ref "C89") (pin "1") (pinfunction "1_1") (pintype "passive"))
      (node (ref "C90") (pin "1") (pinfunction "1_1") (pintype "passive"))
      (node (ref "C91") (pin "1") (pinfunction "1_1") (pintype "passive"))
      (node (ref "C92") (pin "1") (pinfunction "1_1") (pintype "passive"))
      (node (ref "C93") (pin "1") (pinfunction "1_1") (pintype "passive"))
      (node (ref "C94") (pin "1") (pinfunction "1_1") (pintype "passive"))
      (node (ref "C95") (pin "1") (pinfunction "1_1") (pintype "passive"))
      (node (ref "C96") (pin "1") (pinfunction "1_1") (pintype "passive"))
      (node (ref "C97") (pin "1") (pinfunction "1_1") (pintype "passive"))
      (node (ref "C98") (pin "1") (pinfunction "1_1") (pintype "passive"))
      (node (ref "C99") (pin "1") (pinfunction "1_1") (pintype "passive"))
      (node (ref "D1") (pin "1") (pinfunction "A_1") (pintype "passive"))
      (node (ref "L11") (pin "1") (pinfunction "1_1") (pintype "passive"))
      (node (ref "Q1") (pin "2") (pinfunction "E_2") (pintype "passive"))
      (node (ref "R123") (pin "1") (pinfunction "1_1") (pintype "passive"))
      (node (ref "R4") (pin "2") (pinfunction "2_2") (pintype "passive"))
      (node (ref "R82") (pin "2") (pinfunction "2_2") (pintype "passive"))
      (node (ref "R86") (pin "1") (pinfunction "1_1") (pintype "passive"))
      (node (ref "U10") (pin "11") (pinfunction "EP_11") (pintype "passive"))
      (node (ref "U10") (pin "2") (pinfunction "GND_2") (pintype "passive"))
      (node (ref "U10") (pin "7") (pinfunction "PS_GND_7") (pintype "passive"))
      (node (ref "U11") (pin "1") (pinfunction "GND_1") (pintype "passive"))
      (node (ref "U14") (pin "4") (pinfunction "GND_4") (pintype "passive"))
      (node (ref "U15") (pin "4") (pinfunction "GND_4") (pintype "passive"))
      (node (ref "U18") (pin "4") (pinfunction "GND_4") (pintype "passive"))
      (node (ref "U19") (pin "4") (pinfunction "GND_4") (pintype "passive"))
      (node (ref "U4") (pin "1") (pinfunction "GND_1") (pintype "passive"))
      (node (ref "U9") (pin "4") (pinfunction "ON/OFF_4") (pintype "passive"))
      (node (ref "U9") (pin "5") (pinfunction "GND_5") (pintype "passive"))
      (node (ref "U9") (pin "6") (pinfunction "GND_6") (pintype "passive"))
      (node (ref "U9") (pin "7") (pinfunction "GND_7") (pintype "passive"))
      (node (ref "U9") (pin "8") (pinfunction "GND_8") (pintype "passive"))
      (node (ref "U9") (pin "9") (pinfunction "EP-GND_9") (pintype "passive"))
    )
    (net (code "19") (name "Net-(C68-Pad2)") (class "Default")
      (node (ref "C68") (pin "2") (pinfunction "2_2") (pintype "passive"))
      (node (ref "C72") (pin "1") (pinfunction "1_1") (pintype "passive"))
      (node (ref "C73") (pin "2") (pinfunction "2_2") (pintype "passive"))
      (node (ref "FB11") (pin "1") (pinfunction "1_1") (pintype "passive"))
      (node (ref "L4") (pin "2") (pinfunction "2_2") (pintype "passive"))
      (node (ref "R80") (pin "2") (pinfunction "2_2") (pintype "passive"))
    )
    (net (code "20") (name "Net-(C75-Pad1)") (class "Default")
      (node (ref "C75") (pin "1") (pinfunction "1_1") (pintype "passive"))
      (node (ref "L5") (pin "2") (pinfunction "2_2") (pintype "passive"))
      (node (ref "R85") (pin "2") (pinfunction "2_2") (pintype "passive"))
      (node (ref "U12") (pin "1") (pinfunction "S_1") (pintype "passive"))
      (node (ref "U12") (pin "2") (pinfunction "S_2") (pintype "passive"))
      (node (ref "U12") (pin "3") (pinfunction "S_3") (pintype "passive"))
    )
    (net (code "21") (name "Net-(C81-Pad2)") (class "Default")
      (node (ref "C81") (pin "2") (pinfunction "2_2") (pintype "passive"))
      (node (ref "C82") (pin "2") (pinfunction "2_2") (pintype "passive"))
      (node (ref "R83") (pin "2") (pinfunction "2_2") (pintype "passive"))
      (node (ref "R84") (pin "2") (pinfunction "2_2") (pintype "passive"))
      (node (ref "R86") (pin "2") (pinfunction "2_2") (pintype "passive"))
    )
    (net (code "22") (name "Net-(C86-Pad2)") (class "Default")
      (node (ref "C86") (pin "2") (pinfunction "2_2") (pintype "passive"))
      (node (ref "R27") (pin "2") (pinfunction "2_2") (pintype "passive"))
    )
    (net (code "23") (name "Net-(D1-K)") (class "Default")
      (node (ref "D1") (pin "2") (pinfunction "K_2") (pintype "passive"))
      (node (ref "L4") (pin "1") (pinfunction "1_1") (pintype "passive"))
      (node (ref "U9") (pin "2") (pinfunction "VOUT_2") (pintype "passive"))
    )
    (net (code "24") (name "Net-(D2-K)") (class "Default")
      (node (ref "D2") (pin "2") (pinfunction "K_2") (pintype "passive"))
      (node (ref "L11") (pin "2") (pinfunction "2_2") (pintype "passive"))
      (node (ref "U10") (pin "6") (pinfunction "SW_6") (pintype "passive"))
    )
    (net (code "25") (name "Net-(L3-Pad1)") (class "Default")
      (node (ref "L3") (pin "1") (pinfunction "1_1") (pintype "passive"))
      (node (ref "U12") (pin "5") (pinfunction "D_5") (pintype "passive"))
      (node (ref "U12") (pin "6") (pinfunction "D_6") (pintype "passive"))
      (node (ref "U12") (pin "7") (pinfunction "D_7") (pintype "passive"))
      (node (ref "U12") (pin "8") (pinfunction "D_8") (pintype "passive"))
    )
    (net (code "26") (name "Net-(Q1-B)") (class "Default")
      (node (ref "Q1") (pin "1") (pinfunction "B_1") (pintype "passive"))
      (node (ref "R123") (pin "2") (pinfunction "2_2") (pintype "passive"))
      (node (ref "R88") (pin "2") (pinfunction "2_2") (pintype "passive"))
    )
    (net (code "27") (name "Net-(Q1-C)") (class "Default")
      (node (ref "Q1") (pin "3") (pinfunction "C_3") (pintype "passive"))
      (node (ref "R87") (pin "1") (pinfunction "1_1") (pintype "passive"))
    )
    (net (code "28") (name "Net-(U9-FB{slash}ADJ)") (class "Default")
      (node (ref "R80") (pin "1") (pinfunction "1_1") (pintype "passive"))
      (node (ref "R82") (pin "1") (pinfunction "1_1") (pintype "passive"))
      (node (ref "U9") (pin "3") (pinfunction "FB/ADJ_3") (pintype "passive"))
    )
    (net (code "29") (name "Net-(U10-COMP)") (class "Default")
      (node (ref "C97") (pin "2") (pinfunction "2_2") (pintype "passive"))
      (node (ref "U10") (pin "1") (pinfunction "COMP_1") (pintype "passive"))
    )
    (net (code "30") (name "Net-(U10-FB)") (class "Default")
      (node (ref "C86") (pin "1") (pinfunction "1_1") (pintype "passive"))
      (node (ref "R22") (pin "1") (pinfunction "1_1") (pintype "passive"))
      (node (ref "R25") (pin "2") (pinfunction "2_2") (pintype "passive"))
      (node (ref "U10") (pin "9") (pinfunction "FB_9") (pintype "passive"))
    )
    (net (code "31") (name "Net-(U10-VIN)") (class "Default")
      (node (ref "C90") (pin "2") (pinfunction "2_2") (pintype "passive"))
      (node (ref "R23") (pin "2") (pinfunction "2_2") (pintype "passive"))
      (node (ref "U10") (pin "3") (pinfunction "VIN_3") (pintype "passive"))
    )
    (net (code "32") (name "Net-(U10-VREF)") (class "Default")
      (node (ref "C84") (pin "1") (pinfunction "1_1") (pintype "passive"))
      (node (ref "C85") (pin "1") (pinfunction "1_1") (pintype "passive"))
      (node (ref "R22") (pin "2") (pinfunction "2_2") (pintype "passive"))
      (node (ref "U10") (pin "10") (pinfunction "VREF_10") (pintype "passive"))
    )
    (net (code "33") (name "Net-(U12-G)") (class "Default")
      (node (ref "R85") (pin "1") (pinfunction "1_1") (pintype "passive"))
      (node (ref "R87") (pin "2") (pinfunction "2_2") (pintype "passive"))
      (node (ref "U12") (pin "4") (pinfunction "G_4") (pintype "passive"))
    )
    (net (code "34") (name "Net-(U14-OUT)") (class "Default")
      (node (ref "R93") (pin "1") (pinfunction "1_1") (pintype "passive"))
      (node (ref "U14") (pin "5") (pinfunction "OUT_5") (pintype "passive"))
    )
    (net (code "35") (name "Net-(U15-OUT)") (class "Default")
      (node (ref "R94") (pin "1") (pinfunction "1_1") (pintype "passive"))
      (node (ref "U15") (pin "5") (pinfunction "OUT_5") (pintype "passive"))
    )
    (net (code "36") (name "Net-(U18-OUT)") (class "Default")
      (node (ref "R100") (pin "1") (pinfunction "1_1") (pintype "passive"))
      (node (ref "U18") (pin "5") (pinfunction "OUT_5") (pintype "passive"))
    )
    (net (code "37") (name "Net-(U19-OUT)") (class "Default")
      (node (ref "R101") (pin "1") (pinfunction "1_1") (pintype "passive"))
      (node (ref "U19") (pin "5") (pinfunction "OUT_5") (pintype "passive"))
    )
    (net (code "38") (name "VGS1") (class "Default")
      (node (ref "C22") (pin "1") (pinfunction "1_1") (pintype "passive"))
      (node (ref "L7") (pin "2") (pinfunction "2_2") (pintype "passive"))
    )
    (net (code "39") (name "VGS2") (class "Default")
      (node (ref "C23") (pin "1") (pinfunction "1_1") (pintype "passive"))
      (node (ref "L8") (pin "2") (pinfunction "2_2") (pintype "passive"))
    )
    (net (code "40") (name "VGS3") (class "Default")
      (node (ref "C43") (pin "1") (pinfunction "1_1") (pintype "passive"))
      (node (ref "L9") (pin "2") (pinfunction "2_2") (pintype "passive"))
    )
    (net (code "41") (name "VGS4") (class "Default")
      (node (ref "C51") (pin "1") (pinfunction "1_1") (pintype "passive"))
      (node (ref "L10") (pin "2") (pinfunction "2_2") (pintype "passive"))
    )
    (net (code "42") (name "unconnected-(U14-NC-Pad3)") (class "Default")
      (node (ref "U14") (pin "3") (pinfunction "NC_3") (pintype "passive"))
    )
    (net (code "43") (name "unconnected-(U14-NC-Pad6)") (class "Default")
      (node (ref "U14") (pin "6") (pinfunction "NC_6") (pintype "passive"))
    )
    (net (code "44") (name "unconnected-(U14-NC-Pad7)") (class "Default")
      (node (ref "U14") (pin "7") (pinfunction "NC_7") (pintype "passive"))
    )
    (net (code "45") (name "unconnected-(U15-NC-Pad3)") (class "Default")
      (node (ref "U15") (pin "3") (pinfunction "NC_3") (pintype "passive"))
    )
    (net (code "46") (name "unconnected-(U15-NC-Pad6)") (class "Default")
      (node (ref "U15") (pin "6") (pinfunction "NC_6") (pintype "passive"))
    )
    (net (code "47") (name "unconnected-(U15-NC-Pad7)") (class "Default")
      (node (ref "U15") (pin "7") (pinfunction "NC_7") (pintype "passive"))
    )
    (net (code "48") (name "unconnected-(U18-NC-Pad3)") (class "Default")
      (node (ref "U18") (pin "3") (pinfunction "NC_3") (pintype "passive"))
    )
    (net (code "49") (name "unconnected-(U18-NC-Pad6)") (class "Default")
      (node (ref "U18") (pin "6") (pinfunction "NC_6") (pintype "passive"))
    )
    (net (code "50") (name "unconnected-(U18-NC-Pad7)") (class "Default")
      (node (ref "U18") (pin "7") (pinfunction "NC_7") (pintype "passive"))
    )
    (net (code "51") (name "unconnected-(U19-NC-Pad3)") (class "Default")
      (node (ref "U19") (pin "3") (pinfunction "NC_3") (pintype "passive"))
    )
    (net (code "52") (name "unconnected-(U19-NC-Pad6)") (class "Default")
      (node (ref "U19") (pin "6") (pinfunction "NC_6") (pintype "passive"))
    )
    (net (code "53") (name "unconnected-(U19-NC-Pad7)") (class "Default")
      (node (ref "U19") (pin "7") (pinfunction "NC_7") (pintype "passive"))
    )
  )
)
